# M8-LDO_3_3V.net
KiCad netlist of a schematic drawn in Altium Designer
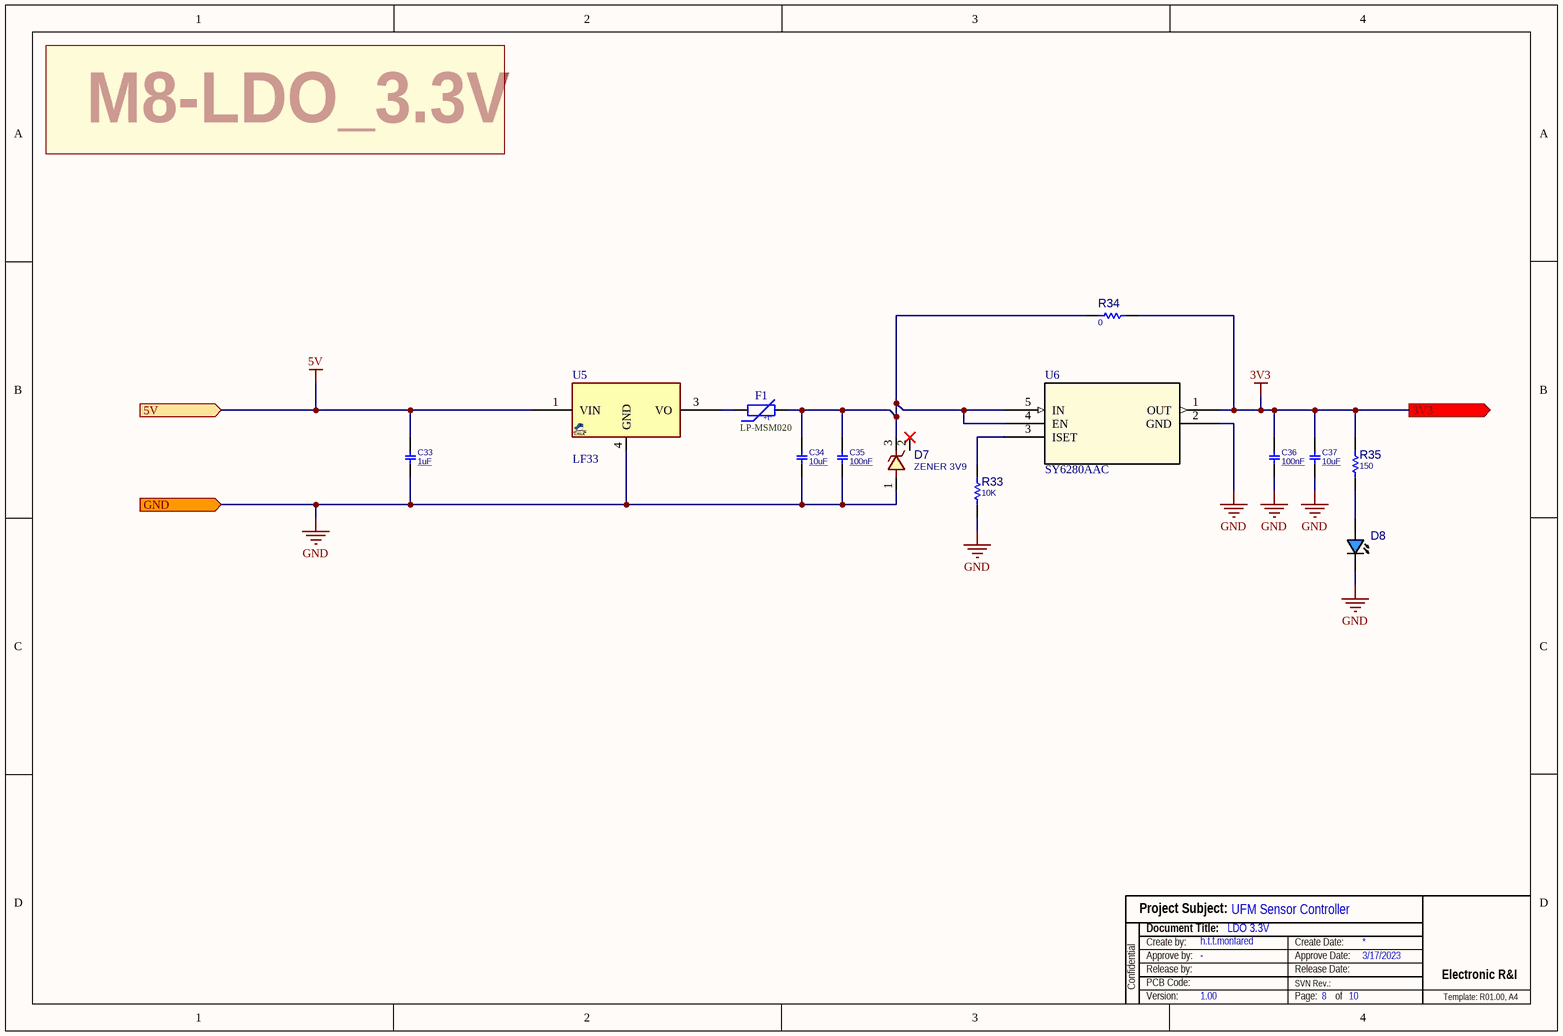
[diagram p0: M8-LDO_3.3V.SchDoc]

(export (version "E")
  (design (tool "Eeschema 10.0.6"))
  (components
    (comp (ref "C33")
      (value "1uF")
      (footprint "C1206")
      (description "CAP, MLCC, 1nF, 50V, C0G, 10%, 0402")
      (fields (field (name "MANF_P#") "MANF_PART#") (field (name "MANF") "Murata"))
      (libsource (lib "passive_smd") (part "CAP_SMD_MLCC"))
    )
    (comp (ref "C34")
      (value "10uF")
      (footprint "C1206")
      (description "CAP, MLCC, 1nF, 50V, C0G, 10%, 0402")
      (fields (field (name "MANF_P#") "MANF_PART#") (field (name "MANF") "Murata"))
      (libsource (lib "passive_smd") (part "CAP_SMD_MLCC"))
    )
    (comp (ref "C35")
      (value "100nF")
      (footprint "C1206")
      (description "CAP, MLCC, 1nF, 50V, C0G, 10%, 0402")
      (fields (field (name "MANF_P#") "MANF_PART#") (field (name "MANF") "Murata"))
      (libsource (lib "passive_smd") (part "CAP_SMD_MLCC"))
    )
    (comp (ref "C36")
      (value "100nF")
      (footprint "C1206")
      (description "CAP, MLCC, 1nF, 50V, C0G, 10%, 0402")
      (fields (field (name "MANF_P#") "MANF_PART#") (field (name "MANF") "Murata"))
      (libsource (lib "passive_smd") (part "CAP_SMD_MLCC"))
    )
    (comp (ref "C37")
      (value "10uF")
      (footprint "C1206")
      (description "CAP, MLCC, 1nF, 50V, C0G, 10%, 0402")
      (fields (field (name "MANF_P#") "MANF_PART#") (field (name "MANF") "Murata"))
      (libsource (lib "passive_smd") (part "CAP_SMD_MLCC"))
    )
    (comp (ref "D7")
      (value "ZENER 3V9")
      (footprint "SOT23_3")
      (description "DIODE, ZENER, 0.25W, 3.9V")
      (fields (field (name "MANF") "NXP") (field (name "MANF_P#") "BZX84-C3V9"))
      (libsource (lib "diode") (part "DIODE_SMD_ZENER_BZX84-C6V2"))
    )
    (comp (ref "D8")
      (value "LED1206BLU")
      (footprint "LED1206BLU")
      (description "LED, SMD, 1206, BLUE")
      (fields (field (name "MANF") "MANF") (field (name "MANF_P#") "MANF_PART#"))
      (libsource (lib "led(diode)") (part "LED_SMD_1206_BLU"))
    )
    (comp (ref "F1")
      (value "LP-MSM020")
      (footprint "F-1812(4532)")
      (description "Thermistor,S,PTC,0.2A,1W,1812")
      (fields (field (name "POWER") "1W"))
      (libsource (lib "Crouse") (part "Res PTC"))
    )
    (comp (ref "R33")
      (value "10K")
      (footprint "R1206")
      (description "RESISTOR, SMD")
      (libsource (lib "passive_smd") (part "RES_SMD"))
    )
    (comp (ref "R34")
      (value "0")
      (footprint "R1206")
      (description "RESISTOR, SMD")
      (libsource (lib "passive_smd") (part "RES_SMD"))
    )
    (comp (ref "R35")
      (value "150")
      (footprint "R1206")
      (description "RESISTOR, SMD")
      (libsource (lib "passive_smd") (part "RES_SMD"))
    )
    (comp (ref "U5")
      (value "LF33")
      (footprint "DPAK_3")
      (description "REG, Linear, LDO0.45V, 0.5A, TO-252")
      (fields (field (name "MANF") "ST"))
      (libsource (lib "pwr_reg_linear") (part "VREG_LFXX_TO252"))
    )
    (comp (ref "U6")
      (value "SY6280AAC")
      (footprint "SOT23_5")
      (description "No Description Available")
      (fields (field (name "COPYRIGHT") "Copyright (C) 2023 Ultra Librarian. All rights reserved."))
      (libsource (lib "SY6280AAC") (part "SY6280AAC"))
    )
  )
  (nets
    (net (code "1") (name "3V3") (class "Default")
      (node (ref "C36") (pin "2") (pinfunction "2_2") (pintype "passive"))
      (node (ref "C37") (pin "2") (pinfunction "2_2") (pintype "passive"))
      (node (ref "R34") (pin "2") (pinfunction "2_2") (pintype "passive"))
      (node (ref "R35") (pin "2") (pinfunction "2_2") (pintype "passive"))
      (node (ref "U6") (pin "1") (pinfunction "OUT_1") (pintype "output"))
    )
    (net (code "2") (name "5V") (class "Default")
      (node (ref "C33") (pin "2") (pinfunction "2_2") (pintype "passive"))
      (node (ref "U5") (pin "1") (pinfunction "VIN_1") (pintype "passive"))
    )
    (net (code "3") (name "GND") (class "Default")
      (node (ref "C33") (pin "1") (pinfunction "1_1") (pintype "passive"))
      (node (ref "C34") (pin "1") (pinfunction "1_1") (pintype "passive"))
      (node (ref "C35") (pin "1") (pinfunction "1_1") (pintype "passive"))
      (node (ref "C36") (pin "1") (pinfunction "1_1") (pintype "passive"))
      (node (ref "C37") (pin "1") (pinfunction "1_1") (pintype "passive"))
      (node (ref "D7") (pin "1") (pinfunction "1_1") (pintype "passive"))
      (node (ref "D8") (pin "2") (pinfunction "CATHODE_2") (pintype "passive"))
      (node (ref "R33") (pin "1") (pinfunction "1_1") (pintype "passive"))
      (node (ref "U5") (pin "4") (pinfunction "GND_4") (pintype "passive"))
      (node (ref "U6") (pin "2") (pinfunction "GND_2") (pintype "passive"))
    )
    (net (code "4") (name "Net-(D8-ANODE)") (class "Default")
      (node (ref "D8") (pin "1") (pinfunction "ANODE_1") (pintype "passive"))
      (node (ref "R35") (pin "1") (pinfunction "1_1") (pintype "passive"))
    )
    (net (code "5") (name "Net-(U5-VO)") (class "Default")
      (node (ref "F1") (pin "1") (pinfunction "1_1") (pintype "passive"))
      (node (ref "U5") (pin "3") (pinfunction "VO_3") (pintype "passive"))
    )
    (net (code "6") (name "Net-(U6-EN)") (class "Default")
      (node (ref "C34") (pin "2") (pinfunction "2_2") (pintype "passive"))
      (node (ref "C35") (pin "2") (pinfunction "2_2") (pintype "passive"))
      (node (ref "D7") (pin "3") (pinfunction "3_3") (pintype "passive"))
      (node (ref "F1") (pin "2") (pinfunction "2_2") (pintype "passive"))
      (node (ref "R34") (pin "1") (pinfunction "1_1") (pintype "passive"))
      (node (ref "U6") (pin "4") (pinfunction "EN_4") (pintype "passive"))
      (node (ref "U6") (pin "5") (pinfunction "IN_5") (pintype "input"))
    )
    (net (code "7") (name "Net-(U6-ISET)") (class "Default")
      (node (ref "R33") (pin "2") (pinfunction "2_2") (pintype "passive"))
      (node (ref "U6") (pin "3") (pinfunction "ISET_3") (pintype "passive"))
    )
    (net (code "8") (name "unconnected-(D7-Pad2)") (class "Default")
      (node (ref "D7") (pin "2") (pinfunction "2_2") (pintype "passive+no_connect"))
    )
  )
)
